# ICS40300-preamp-surfacemount_Rev-E.net
KiCad netlist of a schematic drawn in EAGLE
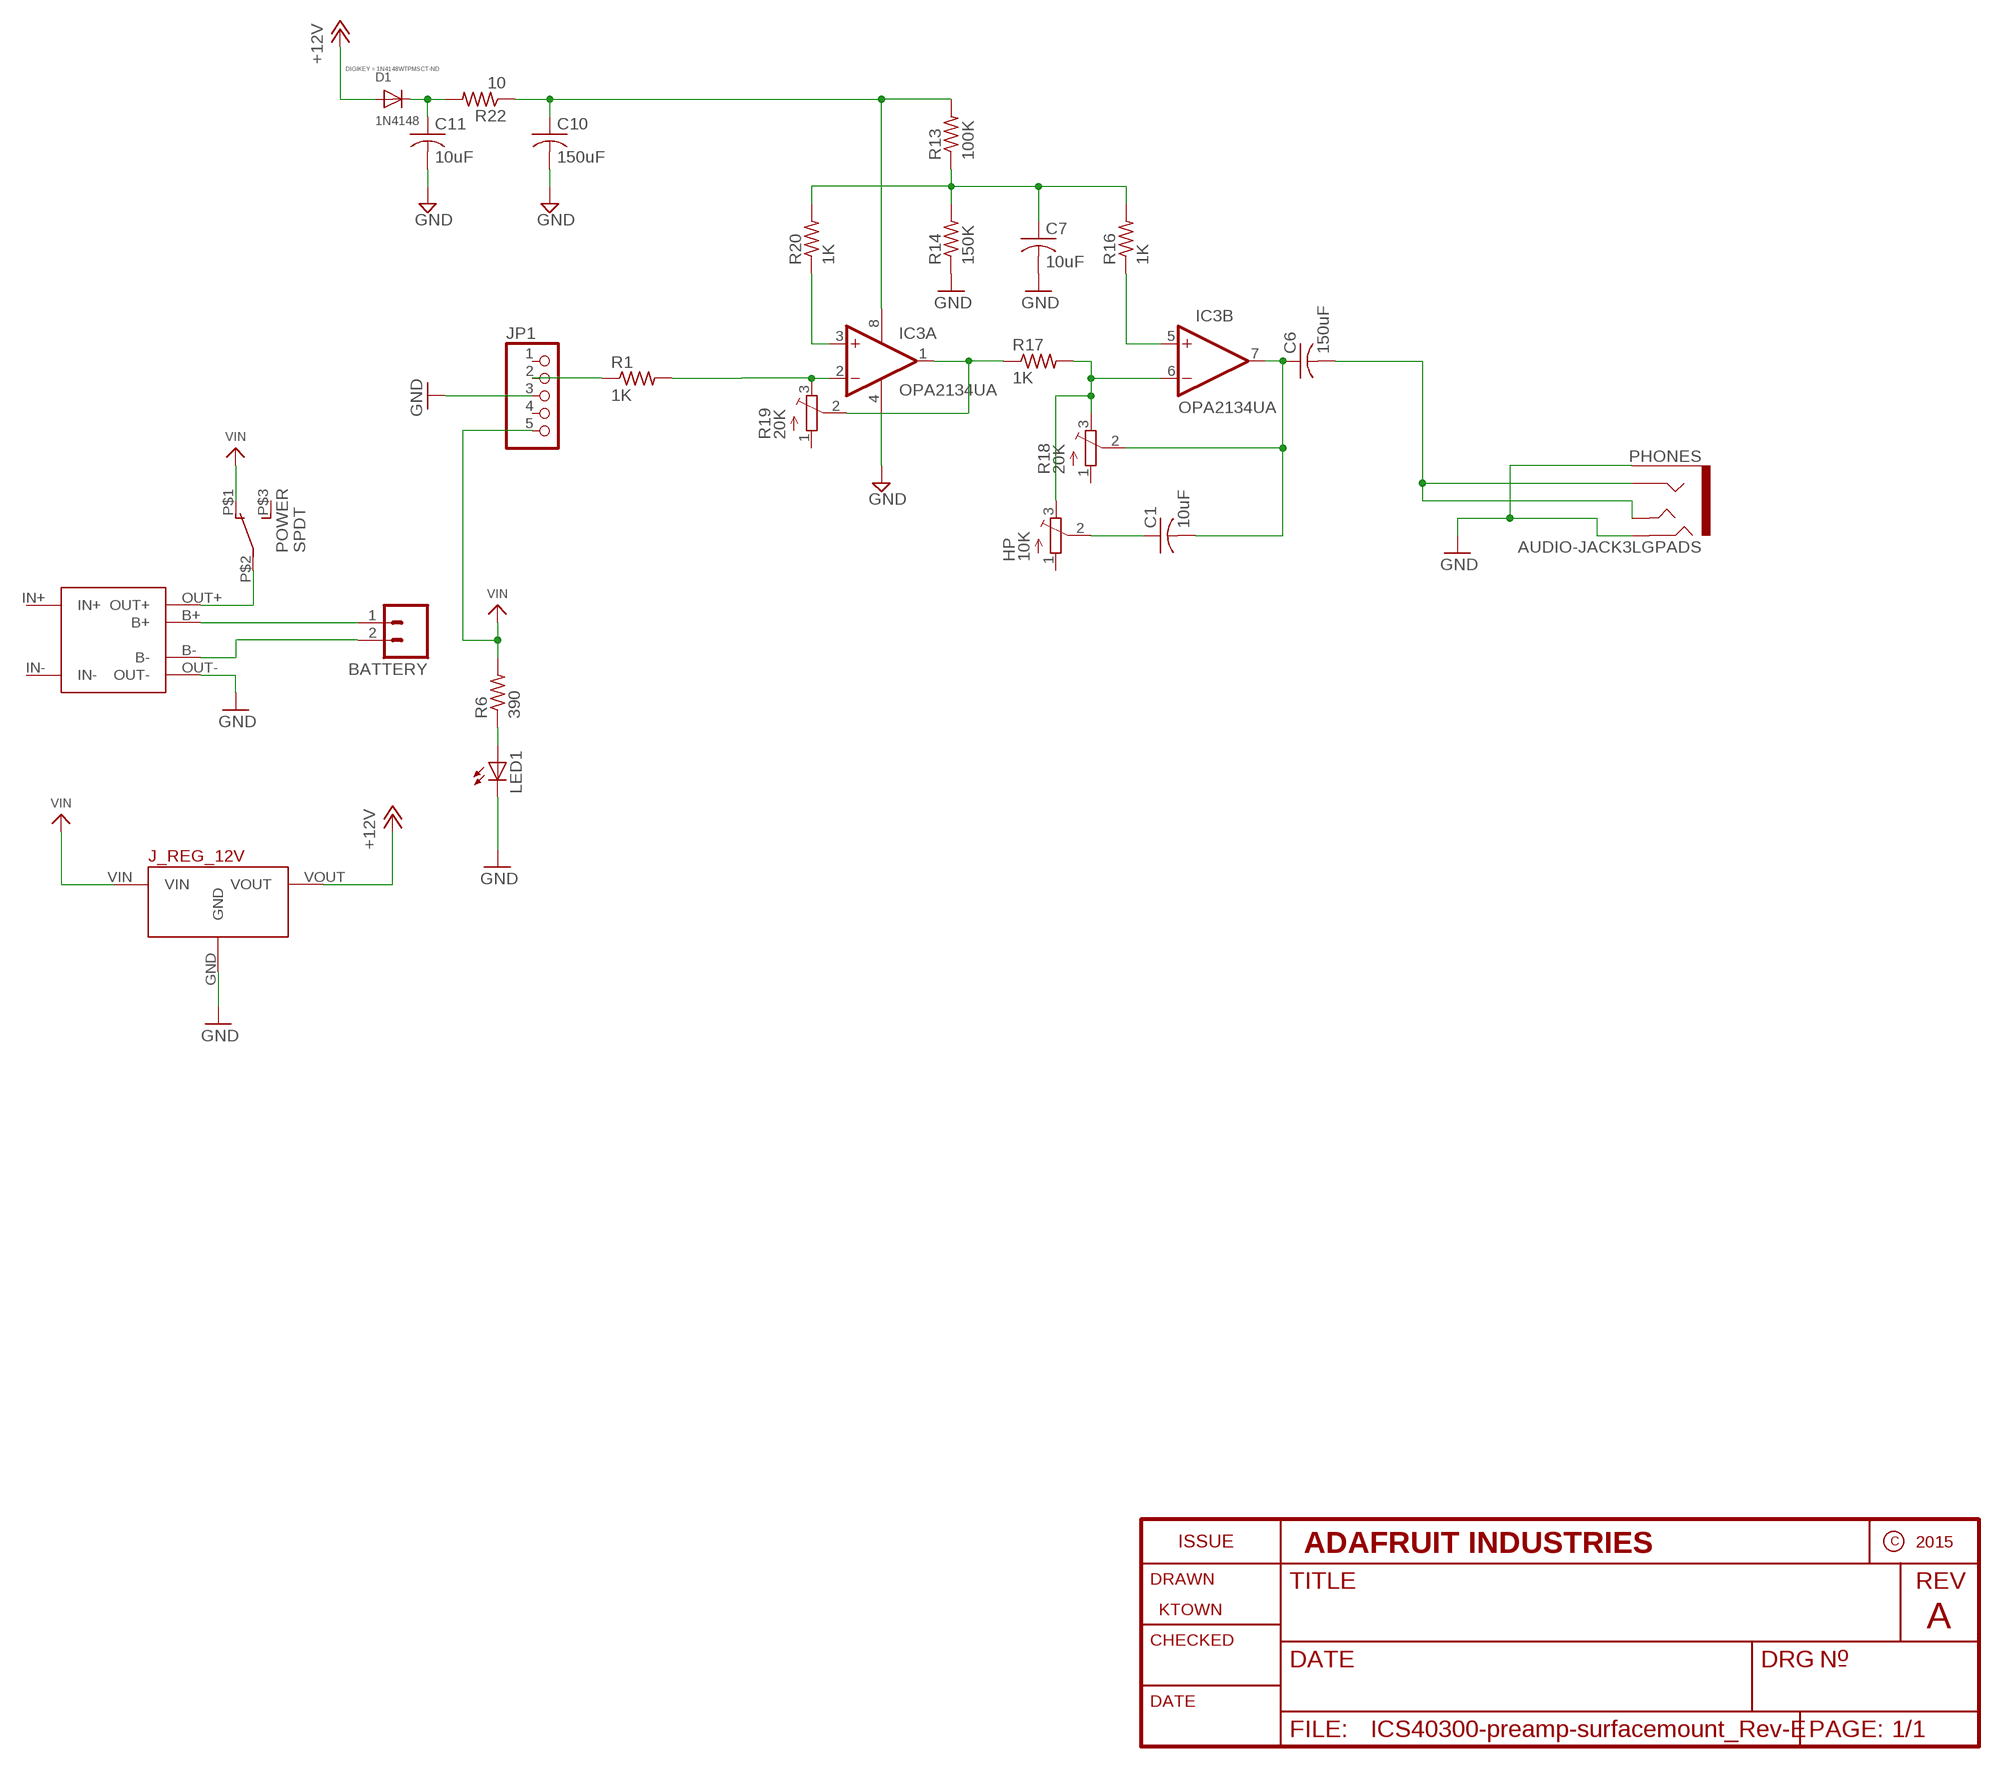
[diagram p0: schematic, sheet 1]

(export (version "E")
  (design (tool "Eeschema 10.0.6"))
  (components
    (comp (ref "BATTERY")
      (value "M02LOCK")
      (footprint "eagle-import:1X02_LOCK")
      (libsource (lib "eagle-import") (part "M02LOCK"))
    )
    (comp (ref "C1")
      (value "10uF")
      (footprint "eagle-import:C0805K")
      (libsource (lib "eagle-import") (part "C-USC0805K"))
    )
    (comp (ref "C6")
      (value "150uF")
      (footprint "eagle-import:CT6032")
      (libsource (lib "eagle-import") (part "C-US6032"))
    )
    (comp (ref "C7")
      (value "10uF")
      (footprint "eagle-import:C0805K")
      (libsource (lib "eagle-import") (part "C-USC0805K"))
    )
    (comp (ref "C10")
      (value "150uF")
      (footprint "eagle-import:CT6032")
      (libsource (lib "eagle-import") (part "C-US6032"))
    )
    (comp (ref "C11")
      (value "10uF")
      (footprint "eagle-import:C0805K")
      (libsource (lib "eagle-import") (part "C-USC0805K"))
    )
    (comp (ref "D1")
      (value "1N4148")
      (footprint "eagle-import:SOD-123")
      (fields (field (name "DIGIKEY") "1N4148WTPMSCT-ND"))
      (libsource (lib "eagle-import") (part "DIODESOD-123"))
    )
    (comp (ref "HP")
      (value "10K")
      (footprint "eagle-import:TC33X")
      (libsource (lib "eagle-import") (part "TRIMPOTTC33X"))
    )
    (comp (ref "IC3")
      (value "OPA2134UA")
      (footprint "eagle-import:SO08")
      (libsource (lib "eagle-import") (part "OPA2UA134"))
    )
    (comp (ref "JP1")
      (value "HEADER-1X576MIL")
      (footprint "eagle-import:1X05_ROUND_76")
      (libsource (lib "eagle-import") (part "HEADER-1X576MIL"))
    )
    (comp (ref "J_REG_12V")
      (value "POLOLU_VOLTAGE_REGULATORS_3PIN")
      (footprint "eagle-import:POLOLU_5V-12V_STEPUP_U3V12F5-U3V12F12")
      (libsource (lib "eagle-import") (part "POLOLU_VOLTAGE_REGULATORS_3PIN"))
    )
    (comp (ref "LED1")
      (value "LED3MM")
      (footprint "eagle-import:LED3MM")
      (libsource (lib "eagle-import") (part "LED3MM"))
    )
    (comp (ref "PHONES")
      (value "AUDIO-JACK3LGPADS")
      (footprint "eagle-import:AUDIO-JACK-TRRS-SMD")
      (libsource (lib "eagle-import") (part "AUDIO-JACK3LGPADS"))
    )
    (comp (ref "POWER")
      (value "SPDT")
      (footprint "eagle-import:SWITCH_SPDT_CL-SB-12B")
      (libsource (lib "eagle-import") (part "SWITCH_SPDTCL-SB-12B"))
    )
    (comp (ref "R1")
      (value "1K")
      (footprint "eagle-import:R0805")
      (libsource (lib "eagle-import") (part "R-US_R0805"))
    )
    (comp (ref "R6")
      (value "390")
      (footprint "eagle-import:R0805")
      (libsource (lib "eagle-import") (part "R-US_R0805"))
    )
    (comp (ref "R13")
      (value "100K")
      (footprint "eagle-import:R0603")
      (libsource (lib "eagle-import") (part "R-US_R0603"))
    )
    (comp (ref "R14")
      (value "150K")
      (footprint "eagle-import:R0603")
      (libsource (lib "eagle-import") (part "R-US_R0603"))
    )
    (comp (ref "R16")
      (value "1K")
      (footprint "eagle-import:R0603")
      (libsource (lib "eagle-import") (part "R-US_R0603"))
    )
    (comp (ref "R17")
      (value "1K")
      (footprint "eagle-import:R0603")
      (libsource (lib "eagle-import") (part "R-US_R0603"))
    )
    (comp (ref "R18")
      (value "20K")
      (footprint "eagle-import:TC33X")
      (libsource (lib "eagle-import") (part "TRIMPOTTC33X"))
    )
    (comp (ref "R19")
      (value "20K")
      (footprint "eagle-import:TC33X")
      (libsource (lib "eagle-import") (part "TRIMPOTTC33X"))
    )
    (comp (ref "R20")
      (value "1K")
      (footprint "eagle-import:R0603")
      (libsource (lib "eagle-import") (part "R-US_R0603"))
    )
    (comp (ref "R22")
      (value "10")
      (footprint "eagle-import:R0603")
      (libsource (lib "eagle-import") (part "R-US_R0603"))
    )
    (comp (ref "U$1")
      (value "TP4056-MODULETP4056")
      (footprint "eagle-import:TP4056-LITHIUM-PROTECTED-MODULE-MOVED-PAD")
      (libsource (lib "eagle-import") (part "TP4056-MODULETP4056"))
    )
  )
  (nets
    (net (code "1") (name "+12V") (class "Default")
      (node (ref "D1") (pin "A") (pinfunction "A_A") (pintype "passive"))
      (node (ref "J_REG_12V") (pin "VOUT") (pinfunction "VOUT_VOUT") (pintype "bidirectional"))
    )
    (net (code "2") (name "/IN+") (class "Default")
      (node (ref "U$1") (pin "IN+") (pinfunction "IN+_IN+") (pintype "power_in"))
    )
    (net (code "3") (name "/IN-") (class "Default")
      (node (ref "U$1") (pin "IN-") (pinfunction "IN-_IN-") (pintype "power_in"))
    )
    (net (code "4") (name "GND") (class "Default")
      (node (ref "C10") (pin "-") (pinfunction "2_-") (pintype "passive"))
      (node (ref "C11") (pin "2") (pinfunction "2_2") (pintype "passive"))
      (node (ref "C7") (pin "2") (pinfunction "2_2") (pintype "passive"))
      (node (ref "IC3") (pin "4") (pinfunction "V-_4") (pintype "power_in"))
      (node (ref "JP1") (pin "3") (pinfunction "3_3") (pintype "passive"))
      (node (ref "J_REG_12V") (pin "GND") (pinfunction "GND_GND") (pintype "bidirectional"))
      (node (ref "LED1") (pin "K") (pinfunction "C_K") (pintype "passive"))
      (node (ref "PHONES") (pin "EARTH") (pinfunction "EARTH_EARTH") (pintype "bidirectional"))
      (node (ref "PHONES") (pin "RING2") (pinfunction "RING2_RING2") (pintype "bidirectional"))
      (node (ref "R14") (pin "1") (pinfunction "1_1") (pintype "passive"))
      (node (ref "U$1") (pin "OUT-") (pinfunction "OUT-_OUT-") (pintype "power_in"))
    )
    (net (code "5") (name "Net-(BATTERY-Pad1)") (class "Default")
      (node (ref "BATTERY") (pin "1") (pinfunction "1_1") (pintype "passive"))
      (node (ref "U$1") (pin "B+") (pinfunction "B+_B+") (pintype "power_in"))
    )
    (net (code "6") (name "Net-(BATTERY-Pad2)") (class "Default")
      (node (ref "BATTERY") (pin "2") (pinfunction "2_2") (pintype "passive"))
      (node (ref "U$1") (pin "B-") (pinfunction "B-_B-") (pintype "power_in"))
    )
    (net (code "7") (name "Net-(C6-1)") (class "Default")
      (node (ref "C1") (pin "2") (pinfunction "2_2") (pintype "passive"))
      (node (ref "C6") (pin "+") (pinfunction "1_+") (pintype "passive"))
      (node (ref "IC3") (pin "7") (pinfunction "OUT_7") (pintype "output"))
      (node (ref "R18") (pin "2") (pinfunction "S_2") (pintype "passive"))
    )
    (net (code "8") (name "Net-(C6-2)") (class "Default")
      (node (ref "C6") (pin "-") (pinfunction "2_-") (pintype "passive"))
      (node (ref "PHONES") (pin "RING1") (pinfunction "RING1_RING1") (pintype "bidirectional"))
      (node (ref "PHONES") (pin "TIP") (pinfunction "TIP_TIP") (pintype "bidirectional"))
    )
    (net (code "9") (name "Net-(C7-Pad1)") (class "Default")
      (node (ref "C7") (pin "1") (pinfunction "1_1") (pintype "passive"))
      (node (ref "R13") (pin "1") (pinfunction "1_1") (pintype "passive"))
      (node (ref "R14") (pin "2") (pinfunction "2_2") (pintype "passive"))
      (node (ref "R16") (pin "2") (pinfunction "2_2") (pintype "passive"))
      (node (ref "R20") (pin "2") (pinfunction "2_2") (pintype "passive"))
    )
    (net (code "10") (name "Net-(C10-1)") (class "Default")
      (node (ref "C10") (pin "+") (pinfunction "1_+") (pintype "passive"))
      (node (ref "IC3") (pin "8") (pinfunction "V+_8") (pintype "power_in"))
      (node (ref "R13") (pin "2") (pinfunction "2_2") (pintype "passive"))
      (node (ref "R22") (pin "1") (pinfunction "1_1") (pintype "passive"))
    )
    (net (code "11") (name "Net-(C11-Pad1)") (class "Default")
      (node (ref "C11") (pin "1") (pinfunction "1_1") (pintype "passive"))
      (node (ref "D1") (pin "C") (pinfunction "C_C") (pintype "passive"))
      (node (ref "R22") (pin "2") (pinfunction "2_2") (pintype "passive"))
    )
    (net (code "12") (name "Net-(HP-E)") (class "Default")
      (node (ref "HP") (pin "3") (pinfunction "E_3") (pintype "passive"))
      (node (ref "IC3") (pin "6") (pinfunction "-IN_6") (pintype "input"))
      (node (ref "R17") (pin "2") (pinfunction "2_2") (pintype "passive"))
      (node (ref "R18") (pin "3") (pinfunction "E_3") (pintype "passive"))
    )
    (net (code "13") (name "Net-(HP-S)") (class "Default")
      (node (ref "C1") (pin "1") (pinfunction "1_1") (pintype "passive"))
      (node (ref "HP") (pin "2") (pinfunction "S_2") (pintype "passive"))
    )
    (net (code "14") (name "Net-(IC3A-+IN)") (class "Default")
      (node (ref "IC3") (pin "3") (pinfunction "+IN_3") (pintype "input"))
      (node (ref "R20") (pin "1") (pinfunction "1_1") (pintype "passive"))
    )
    (net (code "15") (name "Net-(IC3A--IN)") (class "Default")
      (node (ref "IC3") (pin "2") (pinfunction "-IN_2") (pintype "input"))
      (node (ref "R1") (pin "2") (pinfunction "2_2") (pintype "passive"))
      (node (ref "R19") (pin "3") (pinfunction "E_3") (pintype "passive"))
    )
    (net (code "16") (name "Net-(IC3A-OUT)") (class "Default")
      (node (ref "IC3") (pin "1") (pinfunction "OUT_1") (pintype "output"))
      (node (ref "R17") (pin "1") (pinfunction "1_1") (pintype "passive"))
      (node (ref "R19") (pin "2") (pinfunction "S_2") (pintype "passive"))
    )
    (net (code "17") (name "Net-(IC3B-+IN)") (class "Default")
      (node (ref "IC3") (pin "5") (pinfunction "+IN_5") (pintype "input"))
      (node (ref "R16") (pin "1") (pinfunction "1_1") (pintype "passive"))
    )
    (net (code "18") (name "Net-(JP1-Pad2)") (class "Default")
      (node (ref "JP1") (pin "2") (pinfunction "2_2") (pintype "passive"))
      (node (ref "R1") (pin "1") (pinfunction "1_1") (pintype "passive"))
    )
    (net (code "19") (name "Net-(LED1-PadA)") (class "Default")
      (node (ref "LED1") (pin "A") (pinfunction "A_A") (pintype "passive"))
      (node (ref "R6") (pin "1") (pinfunction "1_1") (pintype "passive"))
    )
    (net (code "20") (name "Net-(POWER-2)") (class "Default")
      (node (ref "POWER") (pin "P$2") (pinfunction "2_P$2") (pintype "passive"))
      (node (ref "U$1") (pin "OUT+") (pinfunction "OUT+_OUT+") (pintype "power_in"))
    )
    (net (code "21") (name "VIN") (class "Default")
      (node (ref "JP1") (pin "5") (pinfunction "5_5") (pintype "passive"))
      (node (ref "J_REG_12V") (pin "VIN") (pinfunction "VIN_VIN") (pintype "bidirectional"))
      (node (ref "POWER") (pin "P$1") (pinfunction "1_P$1") (pintype "passive"))
      (node (ref "R6") (pin "2") (pinfunction "2_2") (pintype "passive"))
    )
    (net (code "22") (name "unconnected-(HP-A-Pad1)") (class "Default")
      (node (ref "HP") (pin "1") (pinfunction "A_1") (pintype "passive"))
    )
    (net (code "23") (name "unconnected-(JP1-Pad1)") (class "Default")
      (node (ref "JP1") (pin "1") (pinfunction "1_1") (pintype "passive"))
    )
    (net (code "24") (name "unconnected-(JP1-Pad4)") (class "Default")
      (node (ref "JP1") (pin "4") (pinfunction "4_4") (pintype "passive"))
    )
    (net (code "25") (name "unconnected-(POWER-3-PadP$3)") (class "Default")
      (node (ref "POWER") (pin "P$3") (pinfunction "3_P$3") (pintype "passive"))
    )
    (net (code "26") (name "unconnected-(R18-A-Pad1)") (class "Default")
      (node (ref "R18") (pin "1") (pinfunction "A_1") (pintype "passive"))
    )
    (net (code "27") (name "unconnected-(R19-A-Pad1)") (class "Default")
      (node (ref "R19") (pin "1") (pinfunction "A_1") (pintype "passive"))
    )
  )
)
